# ECB02S2-Kit-V1_0.net
KiCad netlist of a schematic drawn in Altium Designer
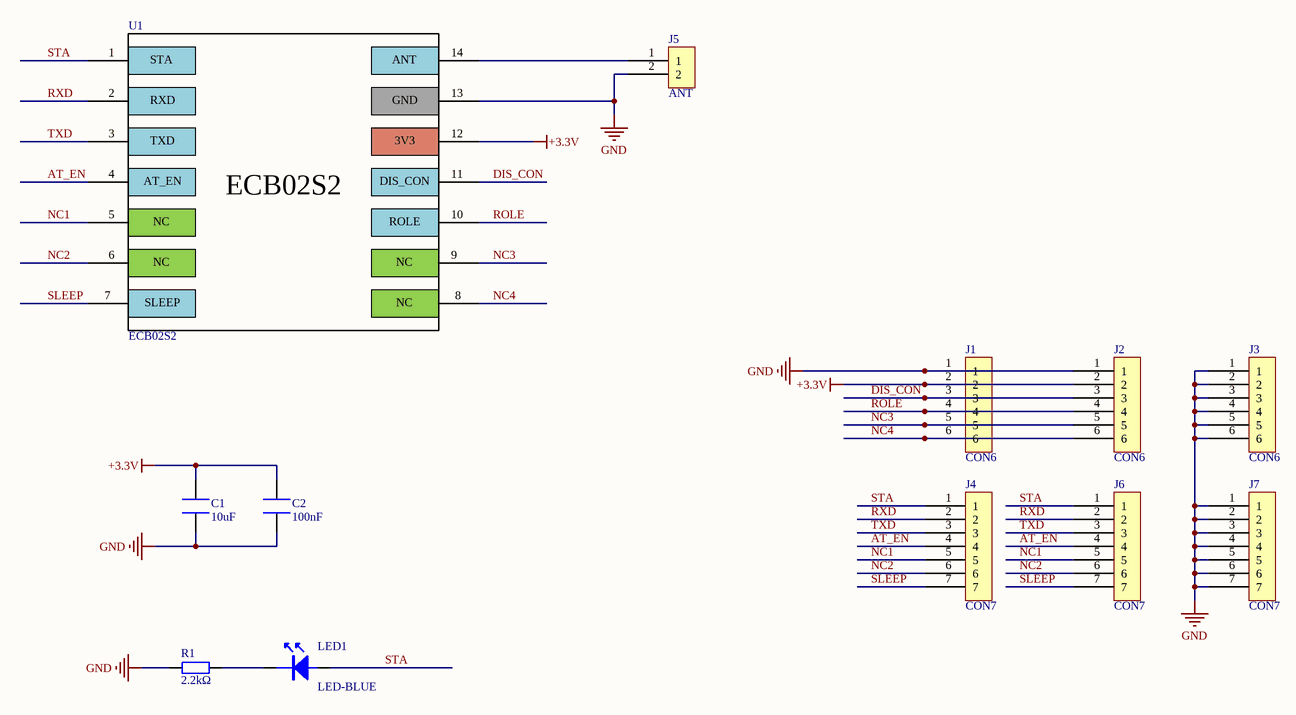
[diagram p0: ECB02S2-Kit-V1.0.SchDoc]

(export (version "E")
  (design (tool "Eeschema 10.0.6"))
  (components
    (comp (ref "C1") (value "10uF") (footprint "0805") (libsource (lib "ECB01-Kit-V1.0") (part "C")))
    (comp (ref "C2") (value "100nF") (footprint "0805") (libsource (lib "ECB01-Kit-V1.0") (part "C")))
    (comp (ref "J1") (value "CON6") (footprint "SIP06") (libsource (lib "ECB02蓝牙模块原理图库") (part "CON6")))
    (comp (ref "J2") (value "CON6") (footprint "SIP06") (libsource (lib "ECB02蓝牙模块原理图库") (part "CON6")))
    (comp (ref "J3") (value "CON6") (footprint "SIP06") (libsource (lib "ECB02蓝牙模块原理图库") (part "CON6")))
    (comp (ref "J4") (value "CON7") (footprint "SIP07") (libsource (lib "ECB02蓝牙模块原理图库") (part "CON7")))
    (comp (ref "J5") (value "ANT") (footprint "ANT-2.4G-1") (libsource (lib "ECB02-Kit-V1.0") (part "ANT")))
    (comp (ref "J6") (value "CON7") (footprint "SIP07") (libsource (lib "ECB02蓝牙模块原理图库") (part "CON7")))
    (comp (ref "J7") (value "CON7") (footprint "SIP07") (libsource (lib "ECB02蓝牙模块原理图库") (part "CON7")))
    (comp (ref "LED1")
      (value "LED-BLUE")
      (footprint "0603-led")
      (libsource (lib "ECB01-Kit-V1.0") (part "LED-0402"))
    )
    (comp (ref "R1") (value "2.2kΩ") (footprint "0603") (libsource (lib "ECB01-Kit-V1.0") (part "R")))
    (comp (ref "U1")
      (value "ECB02S2")
      (footprint "ECB02S2")
      (libsource (lib "ECB02蓝牙模块原理图库") (part "ECB02S2"))
    )
  )
  (nets
    (net (code "1") (name "+3.3V") (class "Default")
      (node (ref "C1") (pin "2") (pinfunction "2_2") (pintype "passive"))
      (node (ref "C2") (pin "2") (pinfunction "2_2") (pintype "passive"))
      (node (ref "J1") (pin "2") (pinfunction "2_2") (pintype "passive"))
      (node (ref "J2") (pin "2") (pinfunction "2_2") (pintype "passive"))
      (node (ref "U1") (pin "12") (pinfunction "12_12") (pintype "passive"))
    )
    (net (code "2") (name "/AT_EN") (class "Default")
      (node (ref "J4") (pin "4") (pinfunction "4_4") (pintype "passive"))
      (node (ref "J6") (pin "4") (pinfunction "4_4") (pintype "passive"))
      (node (ref "U1") (pin "4") (pinfunction "4_4") (pintype "passive"))
    )
    (net (code "3") (name "/DIS_CON") (class "Default")
      (node (ref "J1") (pin "3") (pinfunction "3_3") (pintype "passive"))
      (node (ref "J2") (pin "3") (pinfunction "3_3") (pintype "passive"))
      (node (ref "U1") (pin "11") (pinfunction "11_11") (pintype "passive"))
    )
    (net (code "4") (name "/NC1") (class "Default")
      (node (ref "J4") (pin "5") (pinfunction "5_5") (pintype "passive"))
      (node (ref "J6") (pin "5") (pinfunction "5_5") (pintype "passive"))
      (node (ref "U1") (pin "5") (pinfunction "5_5") (pintype "passive"))
    )
    (net (code "5") (name "/NC2") (class "Default")
      (node (ref "J4") (pin "6") (pinfunction "6_6") (pintype "passive"))
      (node (ref "J6") (pin "6") (pinfunction "6_6") (pintype "passive"))
      (node (ref "U1") (pin "6") (pinfunction "6_6") (pintype "passive"))
    )
    (net (code "6") (name "/NC3") (class "Default")
      (node (ref "J1") (pin "5") (pinfunction "5_5") (pintype "passive"))
      (node (ref "J2") (pin "5") (pinfunction "5_5") (pintype "passive"))
      (node (ref "U1") (pin "9") (pinfunction "9_9") (pintype "passive"))
    )
    (net (code "7") (name "/NC4") (class "Default")
      (node (ref "J1") (pin "6") (pinfunction "6_6") (pintype "passive"))
      (node (ref "J2") (pin "6") (pinfunction "6_6") (pintype "passive"))
      (node (ref "U1") (pin "8") (pinfunction "8_8") (pintype "passive"))
    )
    (net (code "8") (name "/ROLE") (class "Default")
      (node (ref "J1") (pin "4") (pinfunction "4_4") (pintype "passive"))
      (node (ref "J2") (pin "4") (pinfunction "4_4") (pintype "passive"))
      (node (ref "U1") (pin "10") (pinfunction "10_10") (pintype "passive"))
    )
    (net (code "9") (name "/RXD") (class "Default")
      (node (ref "J4") (pin "2") (pinfunction "2_2") (pintype "passive"))
      (node (ref "J6") (pin "2") (pinfunction "2_2") (pintype "passive"))
      (node (ref "U1") (pin "2") (pinfunction "2_2") (pintype "passive"))
    )
    (net (code "10") (name "/SLEEP") (class "Default")
      (node (ref "J4") (pin "7") (pinfunction "7_7") (pintype "passive"))
      (node (ref "J6") (pin "7") (pinfunction "7_7") (pintype "passive"))
      (node (ref "U1") (pin "7") (pinfunction "7_7") (pintype "passive"))
    )
    (net (code "11") (name "/STA") (class "Default")
      (node (ref "J4") (pin "1") (pinfunction "1_1") (pintype "passive"))
      (node (ref "J6") (pin "1") (pinfunction "1_1") (pintype "passive"))
      (node (ref "LED1") (pin "1") (pinfunction "1_1") (pintype "passive"))
      (node (ref "U1") (pin "1") (pinfunction "1_1") (pintype "passive"))
    )
    (net (code "12") (name "/TXD") (class "Default")
      (node (ref "J4") (pin "3") (pinfunction "3_3") (pintype "passive"))
      (node (ref "J6") (pin "3") (pinfunction "3_3") (pintype "passive"))
      (node (ref "U1") (pin "3") (pinfunction "3_3") (pintype "passive"))
    )
    (net (code "13") (name "GND") (class "Default")
      (node (ref "C1") (pin "1") (pinfunction "1_1") (pintype "passive"))
      (node (ref "C2") (pin "1") (pinfunction "1_1") (pintype "passive"))
      (node (ref "J1") (pin "1") (pinfunction "1_1") (pintype "passive"))
      (node (ref "J2") (pin "1") (pinfunction "1_1") (pintype "passive"))
      (node (ref "J3") (pin "1") (pinfunction "1_1") (pintype "passive"))
      (node (ref "J3") (pin "2") (pinfunction "2_2") (pintype "passive"))
      (node (ref "J3") (pin "3") (pinfunction "3_3") (pintype "passive"))
      (node (ref "J3") (pin "4") (pinfunction "4_4") (pintype "passive"))
      (node (ref "J3") (pin "5") (pinfunction "5_5") (pintype "passive"))
      (node (ref "J3") (pin "6") (pinfunction "6_6") (pintype "passive"))
      (node (ref "J5") (pin "2") (pinfunction "2_2") (pintype "passive"))
      (node (ref "J7") (pin "1") (pinfunction "1_1") (pintype "passive"))
      (node (ref "J7") (pin "2") (pinfunction "2_2") (pintype "passive"))
      (node (ref "J7") (pin "3") (pinfunction "3_3") (pintype "passive"))
      (node (ref "J7") (pin "4") (pinfunction "4_4") (pintype "passive"))
      (node (ref "J7") (pin "5") (pinfunction "5_5") (pintype "passive"))
      (node (ref "J7") (pin "6") (pinfunction "6_6") (pintype "passive"))
      (node (ref "J7") (pin "7") (pinfunction "7_7") (pintype "passive"))
      (node (ref "R1") (pin "2") (pinfunction "2_2") (pintype "passive"))
      (node (ref "U1") (pin "13") (pinfunction "13_13") (pintype "passive"))
    )
    (net (code "14") (name "Net-(J5-Pad1)") (class "Default")
      (node (ref "J5") (pin "1") (pinfunction "1_1") (pintype "passive"))
      (node (ref "U1") (pin "14") (pinfunction "14_14") (pintype "passive"))
    )
    (net (code "15") (name "Net-(LED1-Pad2)") (class "Default")
      (node (ref "LED1") (pin "2") (pinfunction "2_2") (pintype "passive"))
      (node (ref "R1") (pin "1") (pinfunction "1_1") (pintype "passive"))
    )
  )
)
